# schematic-easyeda.net
KiCad netlist of a schematic drawn in EasyEDA
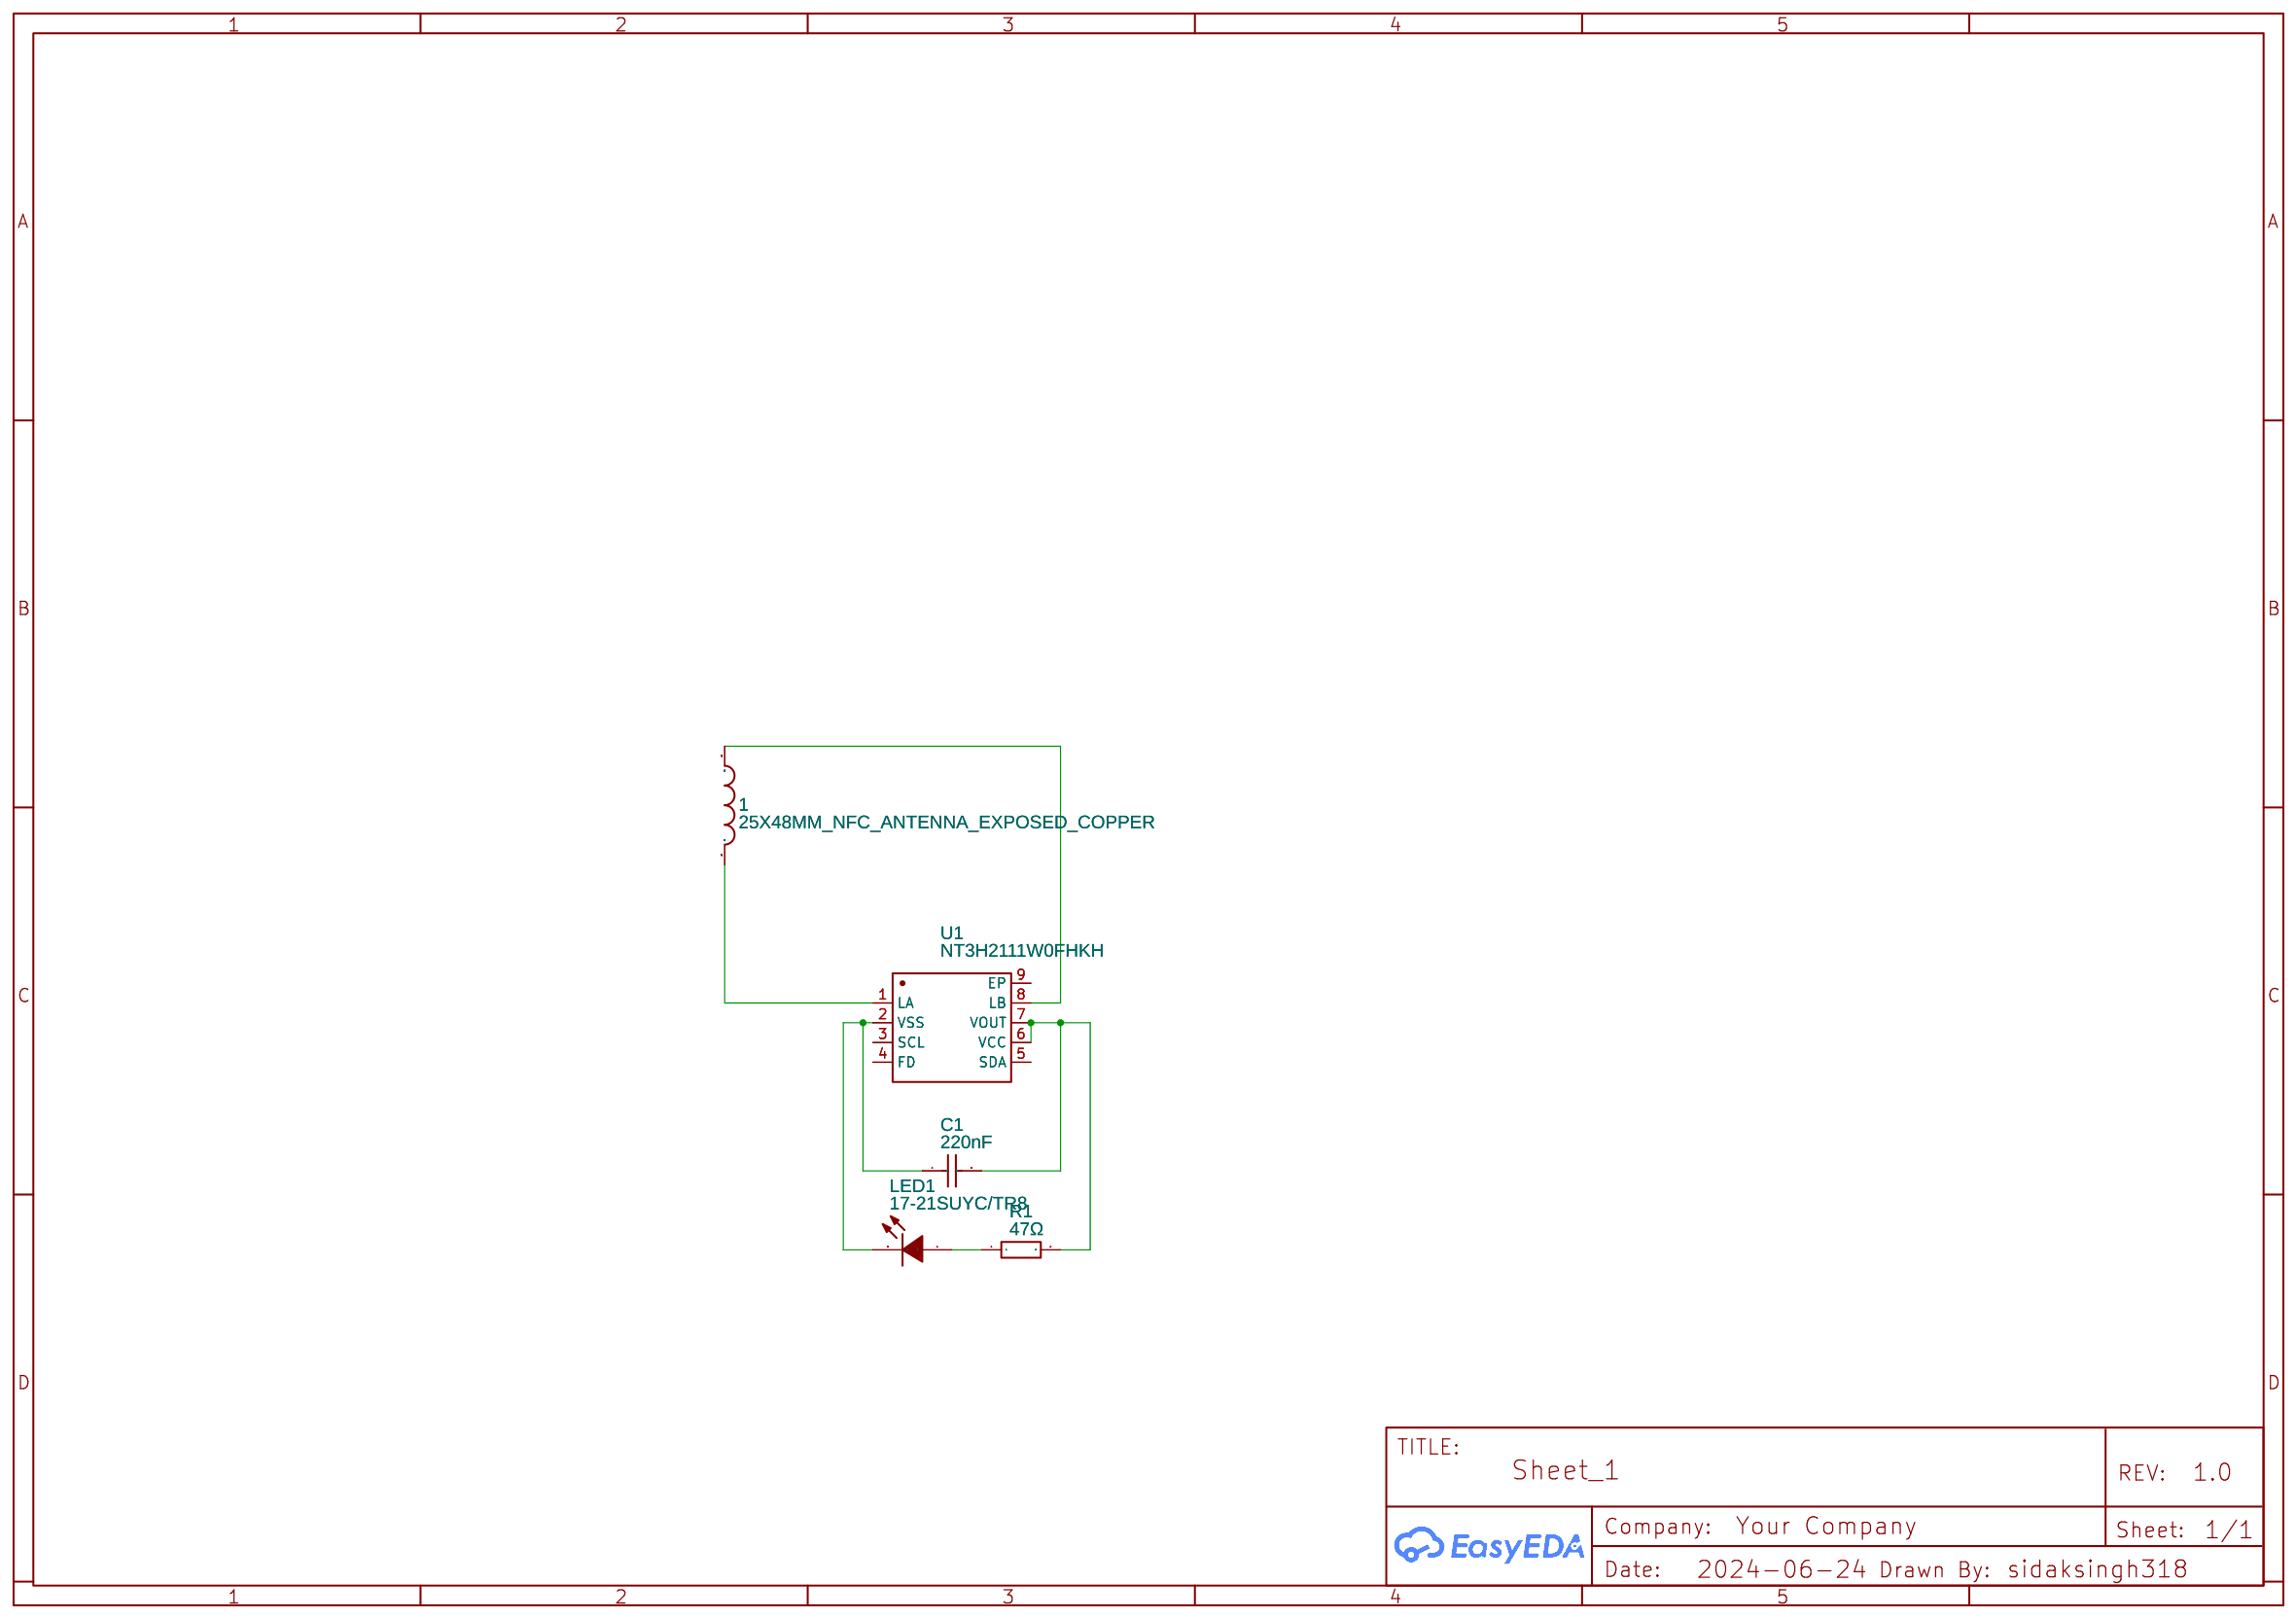
[diagram p0: schematic sheet]

(export (version "E")
  (design (tool "Eeschema 10.0.6"))
  (components
    (comp (ref "1")
      (value "25X48MM_NFC_ANTENNA_EXPOSED_COPPER")
      (libsource (lib "") (part "25X48MM_NFC_ANTENNA_EXPOSED_COPPER"))
    )
    (comp (ref "C1")
      (value "220nF")
      (fields
        (field (name "Manufacturer Part") "CL10B224KA8NNNC")
        (field (name "Manufacturer") "SAMSUNG(三星)")
      )
      (libsource (lib "") (part "CL10B224KA8NNNC"))
    )
    (comp (ref "LED1")
      (value "17-21SUYC/TR8")
      (fields (field (name "Manufacturer Part") "KT-0805黄灯") (field (name "Manufacturer") "KENTO"))
      (libsource (lib "") (part "17-21SUYC/TR8"))
    )
    (comp (ref "R1")
      (value "47Ω")
      (fields
        (field (name "Manufacturer Part") "0603WAF470JT5E")
        (field (name "Manufacturer") "UNI-ROYAL(厚声)")
      )
      (libsource (lib "") (part "0603WAF470JT5E"))
    )
    (comp (ref "U1")
      (value "NT3H2111W0FHKH")
      (fields (field (name "Manufacturer") "NXP(恩智浦)"))
      (libsource (lib "") (part "NT3H2111W0FHKH"))
    )
  )
  (nets
    (net (code "1") (name "Net-(LED1-+)") (class "Default")
      (node (ref "LED1") (pin "1") (pinfunction "+_1") (pintype "unspecified"))
      (node (ref "R1") (pin "1") (pinfunction "1_1") (pintype "input"))
    )
    (net (code "2") (name "Net-(LED1--)") (class "Default")
      (node (ref "C1") (pin "1") (pinfunction "1_1") (pintype "input"))
      (node (ref "LED1") (pin "2") (pinfunction "-_2") (pintype "unspecified"))
      (node (ref "U1") (pin "2") (pinfunction "VSS_2") (pintype "unspecified"))
    )
    (net (code "3") (name "Net-(U1-LA)") (class "Default")
      (node (ref "1") (pin "P$2") (pinfunction "P$2_P$2") (pintype "bidirectional"))
      (node (ref "U1") (pin "1") (pinfunction "LA_1") (pintype "unspecified"))
    )
    (net (code "4") (name "Net-(U1-LB)") (class "Default")
      (node (ref "1") (pin "P$1") (pinfunction "P$1_P$1") (pintype "bidirectional"))
      (node (ref "U1") (pin "8") (pinfunction "LB_8") (pintype "unspecified"))
    )
    (net (code "5") (name "Net-(U1-VCC)") (class "Default")
      (node (ref "C1") (pin "2") (pinfunction "2_2") (pintype "input"))
      (node (ref "R1") (pin "2") (pinfunction "2_2") (pintype "input"))
      (node (ref "U1") (pin "6") (pinfunction "VCC_6") (pintype "unspecified"))
      (node (ref "U1") (pin "7") (pinfunction "VOUT_7") (pintype "unspecified"))
    )
    (net (code "6") (name "unconnected-(U1-EP-Pad9)") (class "Default")
      (node (ref "U1") (pin "9") (pinfunction "EP_9") (pintype "unspecified"))
    )
    (net (code "7") (name "unconnected-(U1-FD-Pad4)") (class "Default")
      (node (ref "U1") (pin "4") (pinfunction "FD_4") (pintype "unspecified"))
    )
    (net (code "8") (name "unconnected-(U1-SCL-Pad3)") (class "Default")
      (node (ref "U1") (pin "3") (pinfunction "SCL_3") (pintype "unspecified"))
    )
    (net (code "9") (name "unconnected-(U1-SDA-Pad5)") (class "Default")
      (node (ref "U1") (pin "5") (pinfunction "SDA_5") (pintype "unspecified"))
    )
  )
)
